# PM_proj.net
KiCad netlist of a schematic drawn in EasyEDA Pro
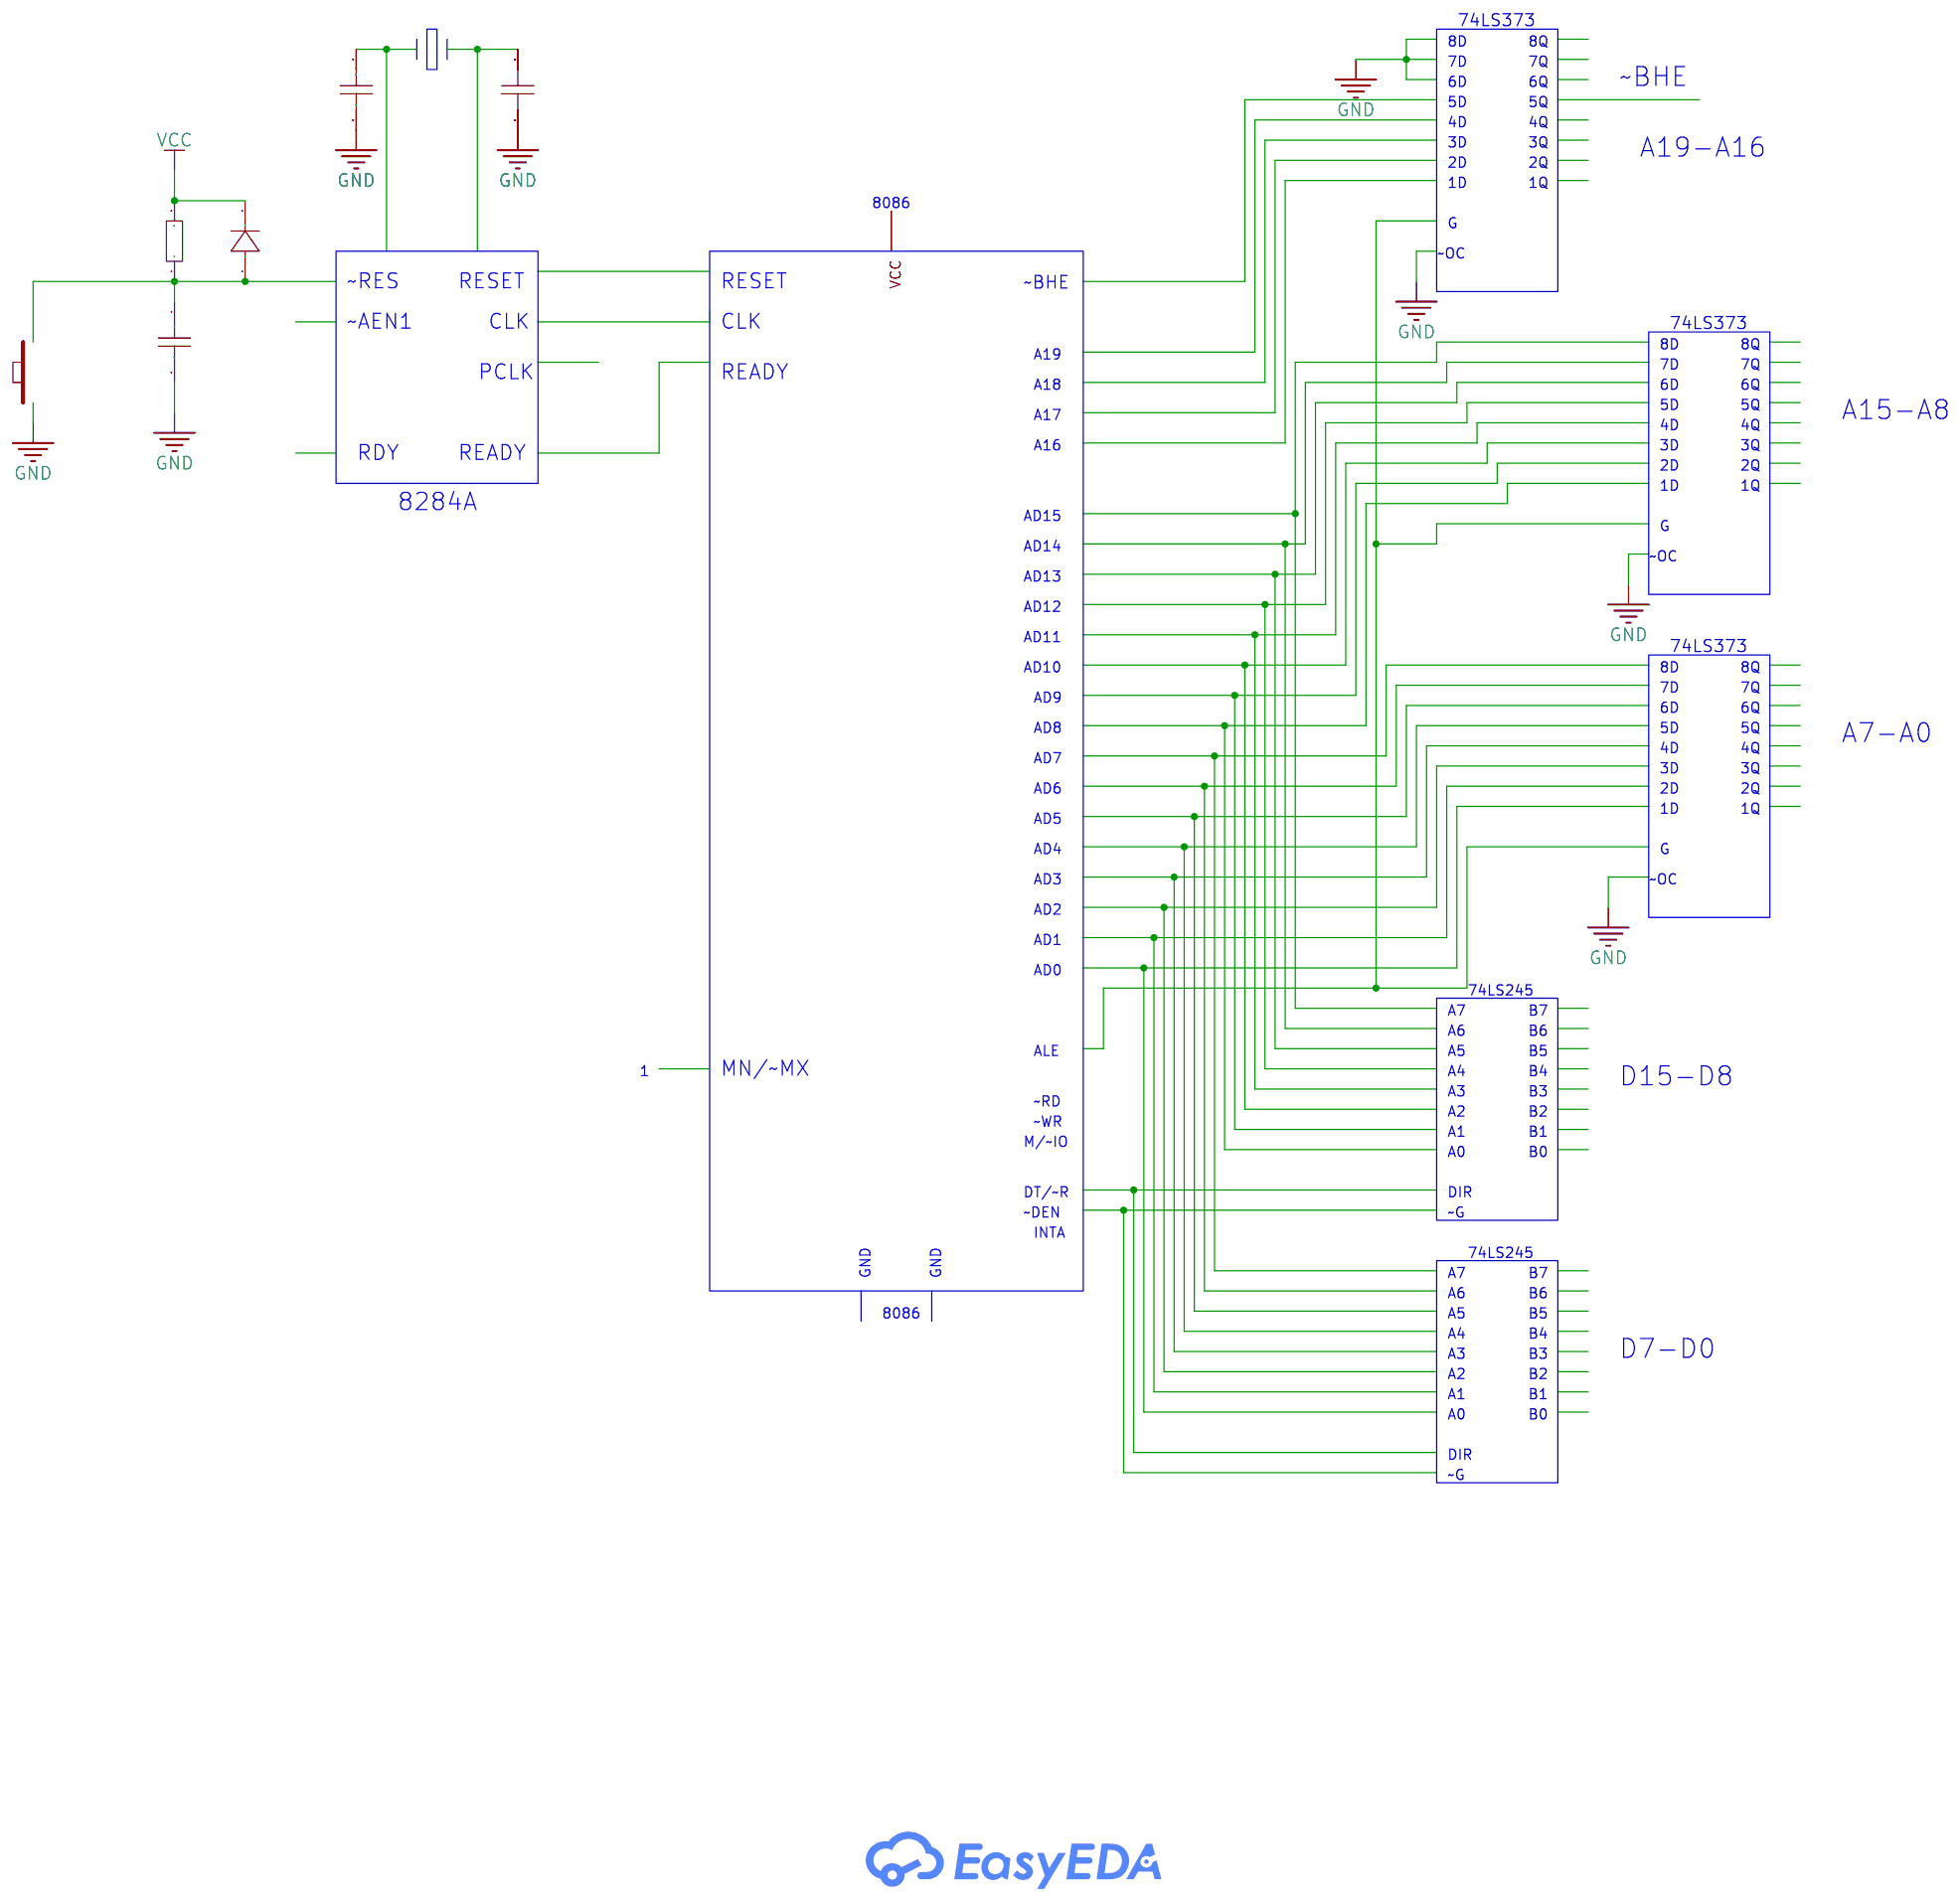
[diagram p0: Unitate Centrala]
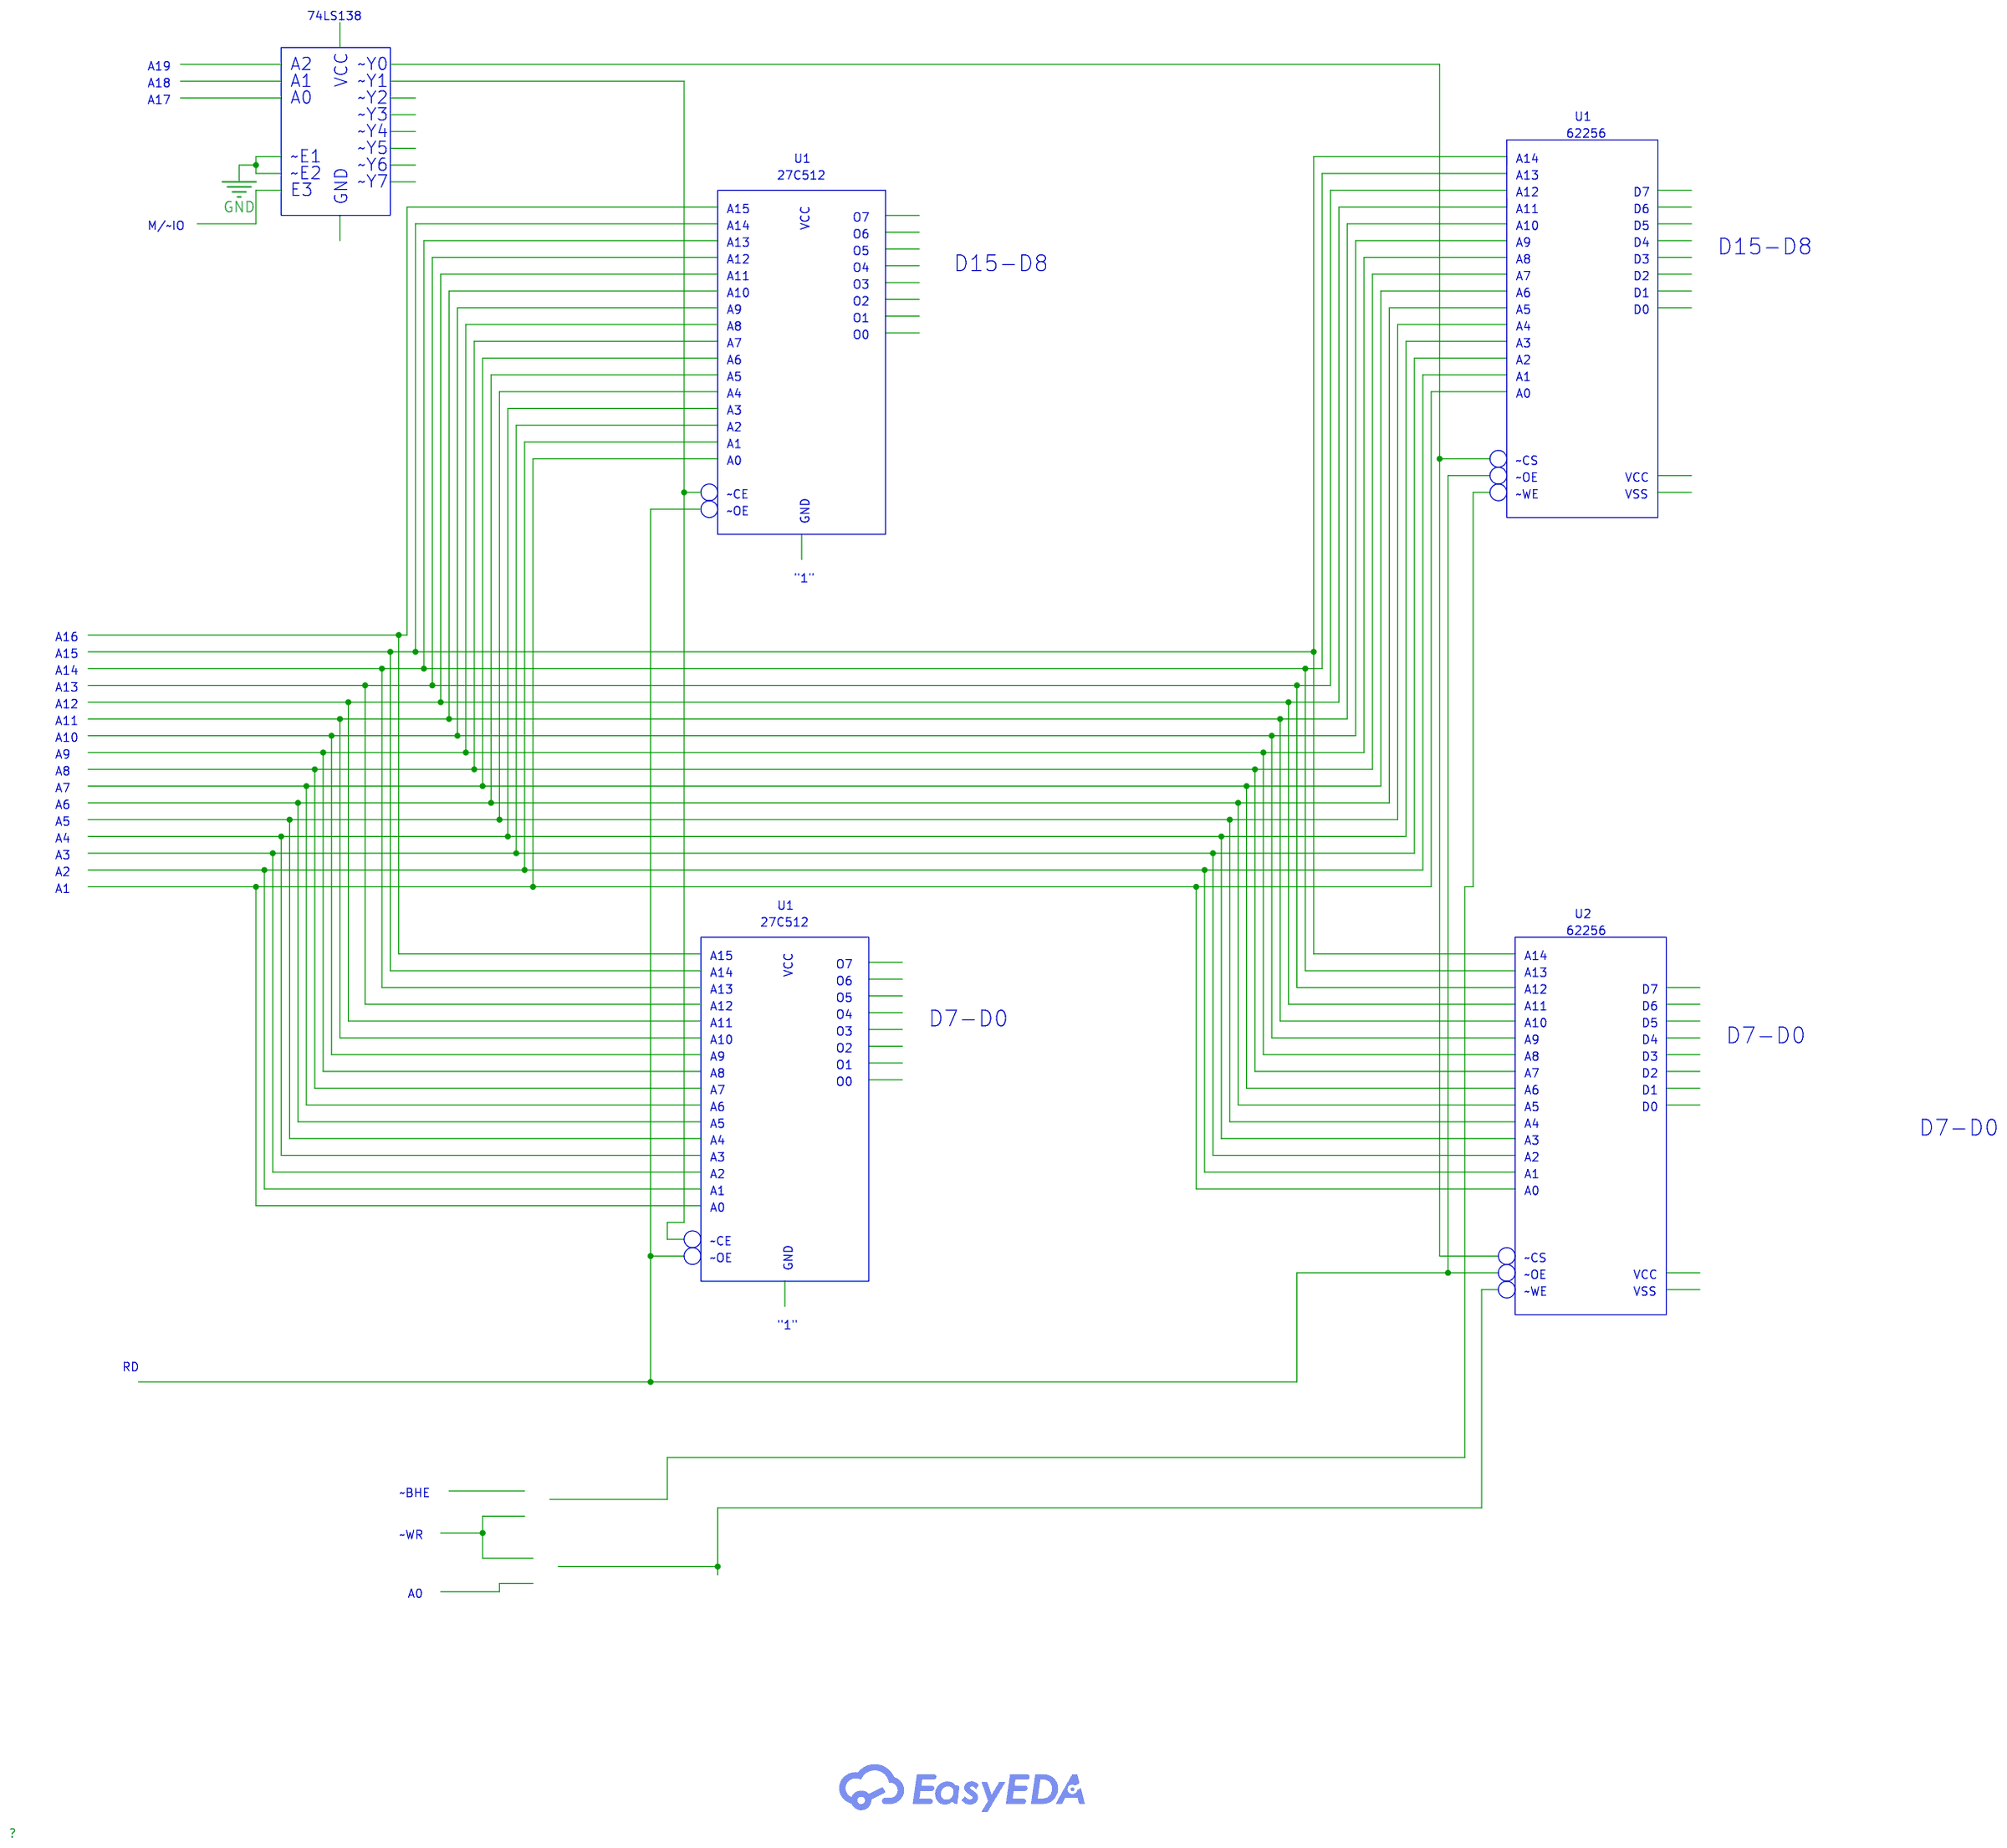
[diagram p1: 2. Conectarea Mem]
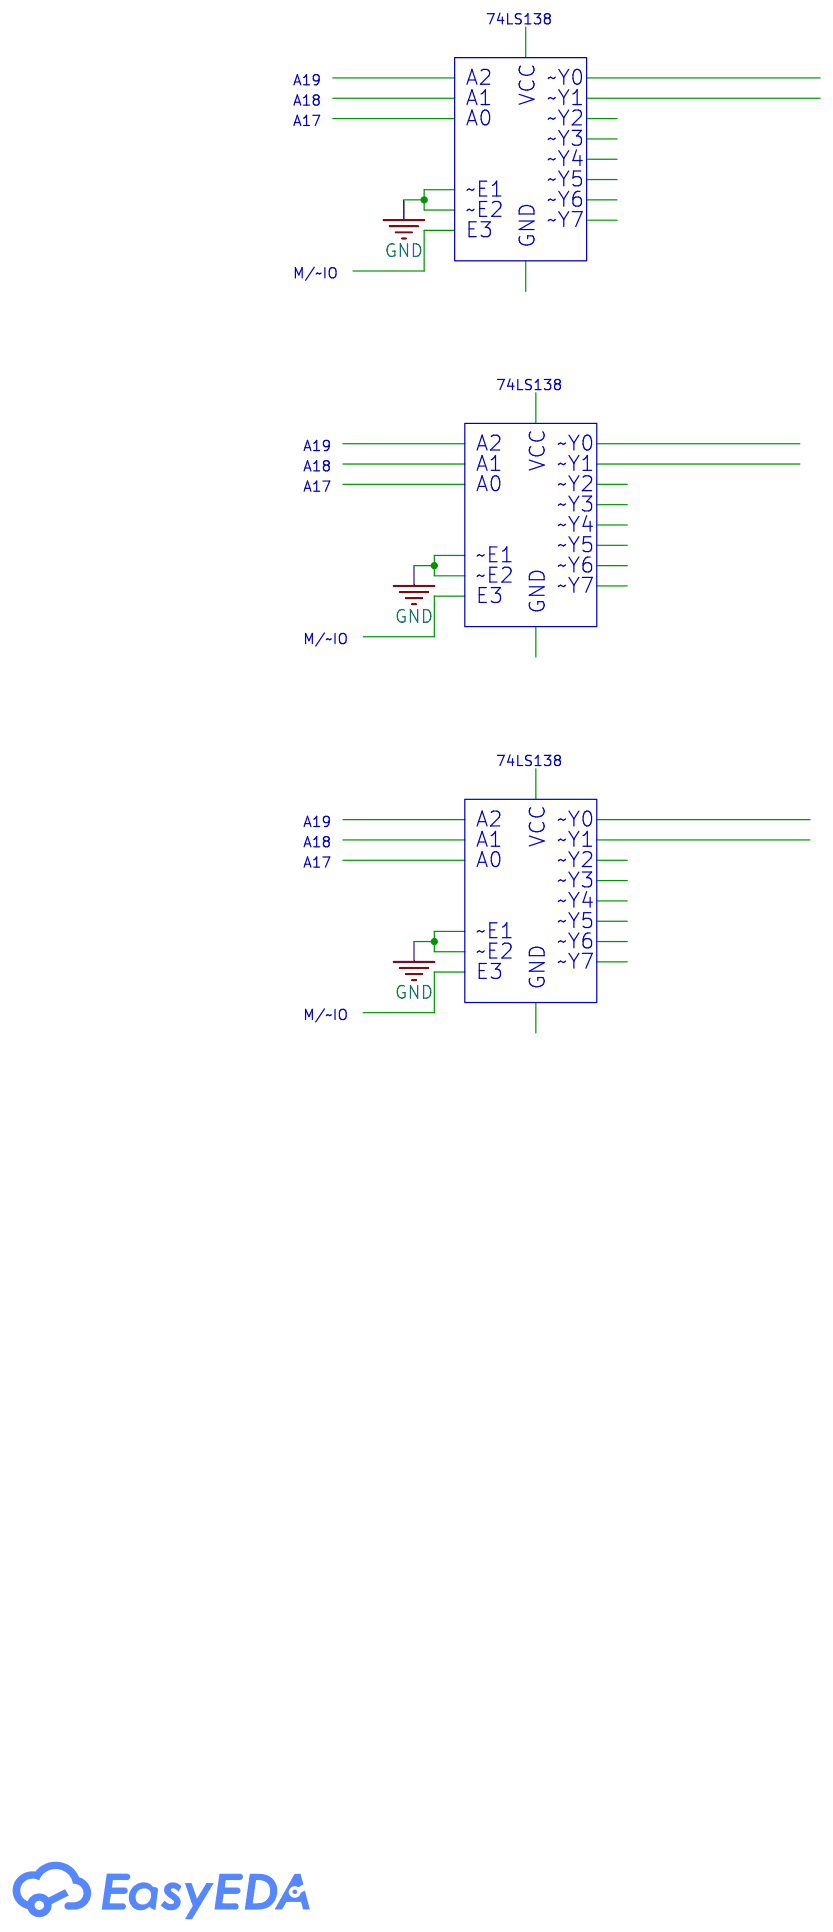
[diagram p2: Decodificarea Porturilor]

(export (version "E")
  (design (tool "Eeschema 10.0.6"))
  (components
    (comp (ref "C1")
      (value "100nF")
      (footprint "easyedapro:C0603")
      (libsource (lib "easyedapro") (part "CAP"))
    )
    (comp (ref "C2")
      (value "100nF")
      (footprint "easyedapro:C0603")
      (libsource (lib "easyedapro") (part "CAP"))
    )
    (comp (ref "C3")
      (value "100nF")
      (footprint "easyedapro:C0603")
      (libsource (lib "easyedapro") (part "CAP"))
    )
    (comp (ref "D1")
      (value "~")
      (footprint "easyedapro:SMA_L4.4-W2.8-LS5.4-RD")
      (libsource (lib "easyedapro") (part "D_1N4007"))
    )
    (comp (ref "R1") (value "10K") (footprint "easyedapro:R0603") (libsource (lib "easyedapro") (part "Res")))
  )
  (nets
    (net (code "1") (name "GND") (class "Default")
      (node (ref "C1") (pin "2") (pinfunction "2_2") (pintype "input"))
      (node (ref "C2") (pin "2") (pinfunction "2_2") (pintype "input"))
      (node (ref "C3") (pin "2") (pinfunction "2_2") (pintype "input"))
    )
    (net (code "2") (name "Net-(D1-A)") (class "Default")
      (node (ref "C1") (pin "1") (pinfunction "1_1") (pintype "input"))
      (node (ref "D1") (pin "2") (pinfunction "A_2") (pintype "input"))
      (node (ref "R1") (pin "1") (pinfunction "1_1") (pintype "input"))
    )
    (net (code "3") (name "VCC") (class "Default")
      (node (ref "D1") (pin "1") (pinfunction "K_1") (pintype "input"))
      (node (ref "R1") (pin "2") (pinfunction "2_2") (pintype "input"))
    )
    (net (code "4") (name "unconnected-(C2-Pad1)") (class "Default")
      (node (ref "C2") (pin "1") (pinfunction "1_1") (pintype "input"))
    )
    (net (code "5") (name "unconnected-(C3-Pad1)") (class "Default")
      (node (ref "C3") (pin "1") (pinfunction "1_1") (pintype "input"))
    )
  )
)
